# Sheet1.net
KiCad netlist of a schematic drawn in Altium Designer
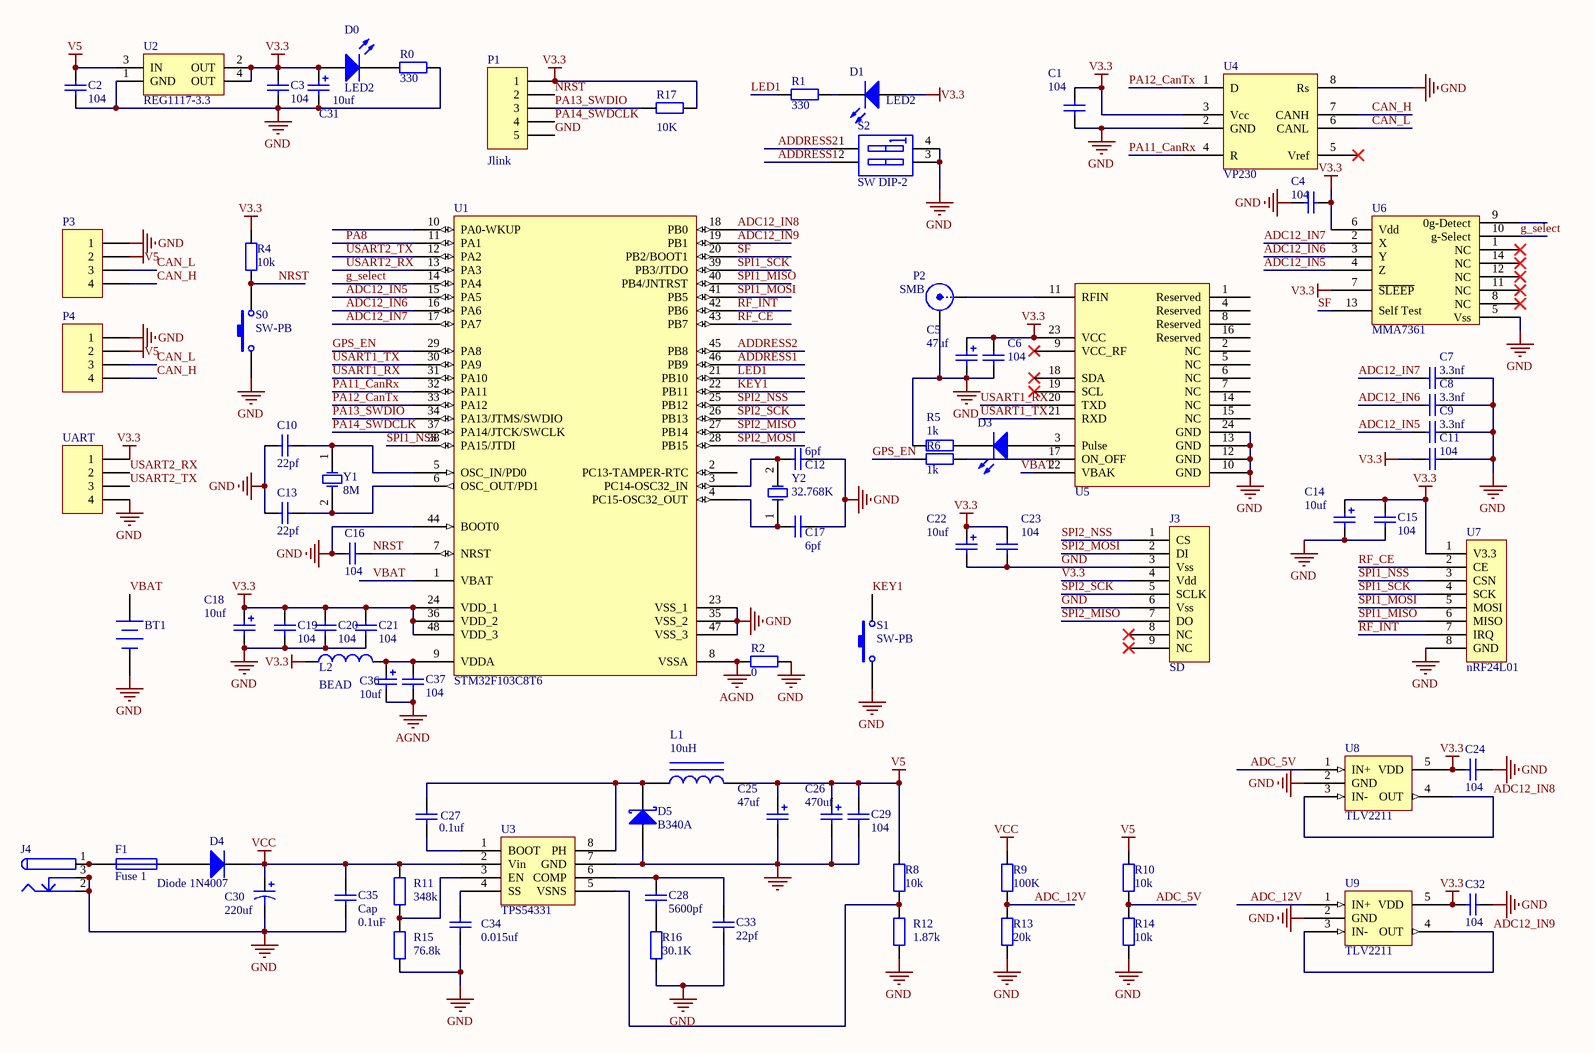
[diagram p0: Sheet1.SchDoc]

(export (version "E")
  (design (tool "Eeschema 10.0.6"))
  (components
    (comp (ref "BT1")
      (value "Battery")
      (footprint "LI1220_1")
      (description "Multicell Battery")
      (fields (field (name "PUBLISHER") "Altium Limited"))
      (libsource (lib "Miscellaneous Devices") (part "Battery"))
    )
    (comp (ref "C1")
      (value "104")
      (footprint "C0805")
      (description "Capacitor")
      (fields (field (name "Comment") "Cap") (field (name "PUBLISHER") "Altium Limited"))
      (libsource (lib "Miscellaneous Devices") (part "Cap"))
    )
    (comp (ref "C2")
      (value "104")
      (footprint "C0805")
      (description "Capacitor")
      (fields (field (name "Comment") "Cap") (field (name "PUBLISHER") "Altium Limited"))
      (libsource (lib "Miscellaneous Devices") (part "Cap"))
    )
    (comp (ref "C3")
      (value "104")
      (footprint "C0805")
      (description "Capacitor")
      (fields (field (name "Comment") "Cap") (field (name "PUBLISHER") "Altium Limited"))
      (libsource (lib "Miscellaneous Devices") (part "Cap"))
    )
    (comp (ref "C4")
      (value "104")
      (footprint "C0805")
      (description "Capacitor")
      (fields (field (name "Comment") "Cap") (field (name "PUBLISHER") "Altium Limited"))
      (libsource (lib "Miscellaneous Devices") (part "Cap"))
    )
    (comp (ref "C5")
      (value "47uf")
      (footprint "1812")
      (description "Polarized Capacitor (Axial)")
      (fields (field (name "Comment") "Cap Pol2") (field (name "PUBLISHER") "Altium Limited"))
      (libsource (lib "Miscellaneous Devices") (part "Cap Pol2"))
    )
    (comp (ref "C6")
      (value "104")
      (footprint "C0805")
      (description "Capacitor")
      (fields (field (name "Comment") "Cap") (field (name "PUBLISHER") "Altium Limited"))
      (libsource (lib "Miscellaneous Devices") (part "Cap"))
    )
    (comp (ref "C7")
      (value "3.3nf")
      (footprint "C0805")
      (description "Capacitor")
      (fields (field (name "Comment") "Cap") (field (name "PUBLISHER") "Altium Limited"))
      (libsource (lib "Miscellaneous Devices") (part "Cap"))
    )
    (comp (ref "C8")
      (value "3.3nf")
      (footprint "C0805")
      (description "Capacitor")
      (fields (field (name "Comment") "Cap") (field (name "PUBLISHER") "Altium Limited"))
      (libsource (lib "Miscellaneous Devices") (part "Cap"))
    )
    (comp (ref "C9")
      (value "3.3nf")
      (footprint "C0805")
      (description "Capacitor")
      (fields (field (name "Comment") "Cap") (field (name "PUBLISHER") "Altium Limited"))
      (libsource (lib "Miscellaneous Devices") (part "Cap"))
    )
    (comp (ref "C10")
      (value "22pf")
      (footprint "C0805")
      (description "Capacitor")
      (fields (field (name "Comment") "Cap") (field (name "PUBLISHER") "Altium Limited"))
      (libsource (lib "Miscellaneous Devices") (part "Cap"))
    )
    (comp (ref "C11")
      (value "104")
      (footprint "C0805")
      (description "Capacitor")
      (fields (field (name "Comment") "Cap") (field (name "PUBLISHER") "Altium Limited"))
      (libsource (lib "Miscellaneous Devices") (part "Cap"))
    )
    (comp (ref "C12")
      (value "6pf")
      (footprint "C0805")
      (description "Capacitor")
      (fields (field (name "Comment") "Cap") (field (name "PUBLISHER") "Altium Limited"))
      (libsource (lib "Miscellaneous Devices") (part "Cap"))
    )
    (comp (ref "C13")
      (value "22pf")
      (footprint "C0805")
      (description "Capacitor")
      (fields (field (name "Comment") "Cap") (field (name "PUBLISHER") "Altium Limited"))
      (libsource (lib "Miscellaneous Devices") (part "Cap"))
    )
    (comp (ref "C14")
      (value "10uf")
      (footprint "1206")
      (description "Polarized Capacitor (Axial)")
      (fields (field (name "Comment") "Cap Pol2") (field (name "PUBLISHER") "Altium Limited"))
      (libsource (lib "Miscellaneous Devices") (part "Cap Pol2"))
    )
    (comp (ref "C15")
      (value "104")
      (footprint "C0805")
      (description "Capacitor")
      (fields (field (name "Comment") "Cap") (field (name "PUBLISHER") "Altium Limited"))
      (libsource (lib "Miscellaneous Devices") (part "Cap"))
    )
    (comp (ref "C16")
      (value "104")
      (footprint "C0805")
      (description "Capacitor")
      (fields (field (name "Comment") "Cap") (field (name "PUBLISHER") "Altium Limited"))
      (libsource (lib "Miscellaneous Devices") (part "Cap"))
    )
    (comp (ref "C17")
      (value "6pf")
      (footprint "C0805")
      (description "Capacitor")
      (fields (field (name "Comment") "Cap") (field (name "PUBLISHER") "Altium Limited"))
      (libsource (lib "Miscellaneous Devices") (part "Cap"))
    )
    (comp (ref "C18")
      (value "10uf")
      (footprint "1206")
      (description "Polarized Capacitor (Axial)")
      (fields (field (name "Comment") "Cap Pol2") (field (name "PUBLISHER") "Altium Limited"))
      (libsource (lib "Miscellaneous Devices") (part "Cap Pol2"))
    )
    (comp (ref "C19")
      (value "104")
      (footprint "C0805")
      (description "Capacitor")
      (fields (field (name "Comment") "Cap") (field (name "PUBLISHER") "Altium Limited"))
      (libsource (lib "Miscellaneous Devices") (part "Cap"))
    )
    (comp (ref "C20")
      (value "104")
      (footprint "C0805")
      (description "Capacitor")
      (fields (field (name "Comment") "Cap") (field (name "PUBLISHER") "Altium Limited"))
      (libsource (lib "Miscellaneous Devices") (part "Cap"))
    )
    (comp (ref "C21")
      (value "104")
      (footprint "C0805")
      (description "Capacitor")
      (fields (field (name "Comment") "Cap") (field (name "PUBLISHER") "Altium Limited"))
      (libsource (lib "Miscellaneous Devices") (part "Cap"))
    )
    (comp (ref "C22")
      (value "10uf")
      (footprint "1206")
      (description "Polarized Capacitor (Axial)")
      (fields (field (name "Comment") "Cap Pol2") (field (name "PUBLISHER") "Altium Limited"))
      (libsource (lib "Miscellaneous Devices") (part "Cap Pol2"))
    )
    (comp (ref "C23")
      (value "104")
      (footprint "C0805")
      (description "Capacitor")
      (fields (field (name "Comment") "Cap") (field (name "PUBLISHER") "Altium Limited"))
      (libsource (lib "Miscellaneous Devices") (part "Cap"))
    )
    (comp (ref "C24")
      (value "104")
      (footprint "C0805")
      (description "Capacitor")
      (fields (field (name "Comment") "Cap") (field (name "PUBLISHER") "Altium Limited"))
      (libsource (lib "Miscellaneous Devices") (part "Cap"))
    )
    (comp (ref "C25")
      (value "47uf")
      (footprint "1812")
      (description "Polarized Capacitor (Axial)")
      (fields (field (name "Comment") "Cap Pol2") (field (name "PUBLISHER") "Altium Limited"))
      (libsource (lib "Miscellaneous Devices") (part "Cap Pol2"))
    )
    (comp (ref "C26")
      (value "470uf")
      (footprint "Cap8*8")
      (description "Polarized Capacitor (Axial)")
      (fields (field (name "Comment") "Cap Pol2") (field (name "PUBLISHER") "Altium Limited"))
      (libsource (lib "Miscellaneous Devices") (part "Cap Pol2"))
    )
    (comp (ref "C27")
      (value "0.1uf")
      (footprint "C0805")
      (description "Capacitor")
      (fields (field (name "Comment") "Cap") (field (name "PUBLISHER") "Altium Limited"))
      (libsource (lib "Miscellaneous Devices") (part "Cap"))
    )
    (comp (ref "C28")
      (value "5600pf")
      (footprint "C0805")
      (description "Capacitor")
      (fields (field (name "Comment") "Cap") (field (name "PUBLISHER") "Altium Limited"))
      (libsource (lib "Miscellaneous Devices") (part "Cap"))
    )
    (comp (ref "C29")
      (value "104")
      (footprint "C0805")
      (description "Capacitor")
      (fields (field (name "Comment") "Cap") (field (name "PUBLISHER") "Altium Limited"))
      (libsource (lib "Miscellaneous Devices") (part "Cap"))
    )
    (comp (ref "C30")
      (value "220uf")
      (footprint "Cap8*8")
      (description "Polarized Capacitor (Radial)")
      (fields (field (name "Comment") "Cap Pol1") (field (name "PUBLISHER") "Altium Limited"))
      (libsource (lib "Miscellaneous Devices") (part "Cap Pol1"))
    )
    (comp (ref "C31")
      (value "10uf")
      (footprint "1206")
      (description "Polarized Capacitor (Axial)")
      (fields (field (name "Comment") "Cap Pol2") (field (name "PUBLISHER") "Altium Limited"))
      (libsource (lib "Miscellaneous Devices") (part "Cap Pol2"))
    )
    (comp (ref "C32")
      (value "104")
      (footprint "C0805")
      (description "Capacitor")
      (fields (field (name "Comment") "Cap") (field (name "PUBLISHER") "Altium Limited"))
      (libsource (lib "Miscellaneous Devices") (part "Cap"))
    )
    (comp (ref "C33")
      (value "22pf")
      (footprint "C0805")
      (description "Capacitor")
      (fields (field (name "Comment") "Cap") (field (name "PUBLISHER") "Altium Limited"))
      (libsource (lib "Miscellaneous Devices") (part "Cap"))
    )
    (comp (ref "C34")
      (value "0.015uf")
      (footprint "C0805")
      (description "Capacitor")
      (fields (field (name "Comment") "Cap") (field (name "PUBLISHER") "Altium Limited"))
      (libsource (lib "Miscellaneous Devices") (part "Cap"))
    )
    (comp (ref "C35")
      (value "Cap")
      (footprint "C0805")
      (description "Capacitor")
      (fields (field (name "ALTIUM_VALUE") "0.1uF") (field (name "PUBLISHER") "Altium Limited"))
      (libsource (lib "Miscellaneous Devices") (part "Cap"))
    )
    (comp (ref "C36")
      (value "10uf")
      (footprint "1206")
      (description "Polarized Capacitor (Axial)")
      (fields (field (name "Comment") "Cap Pol2") (field (name "PUBLISHER") "Altium Limited"))
      (libsource (lib "Miscellaneous Devices") (part "Cap Pol2"))
    )
    (comp (ref "C37")
      (value "104")
      (footprint "C0805")
      (description "Capacitor")
      (fields (field (name "Comment") "Cap") (field (name "PUBLISHER") "Altium Limited"))
      (libsource (lib "Miscellaneous Devices") (part "Cap"))
    )
    (comp (ref "D0")
      (value "LED2")
      (footprint "C0805")
      (description "Typical RED, GREEN, YELLOW, AMBER GaAs LED")
      (fields (field (name "PUBLISHER") "Altium Limited"))
      (libsource (lib "Miscellaneous Devices") (part "LED2"))
    )
    (comp (ref "D1")
      (value "LED2")
      (footprint "C0805")
      (description "Typical RED, GREEN, YELLOW, AMBER GaAs LED")
      (fields (field (name "PUBLISHER") "Altium Limited"))
      (libsource (lib "Miscellaneous Devices") (part "LED2"))
    )
    (comp (ref "D3")
      (value "LED2")
      (footprint "C0805")
      (description "Typical RED, GREEN, YELLOW, AMBER GaAs LED")
      (fields (field (name "PUBLISHER") "Altium Limited"))
      (libsource (lib "Miscellaneous Devices") (part "LED2"))
    )
    (comp (ref "D4")
      (value "Diode 1N4007")
      (footprint "SMB")
      (description "1 Amp General Purpose Rectifier")
      (fields (field (name "PUBLISHER") "Altium Limited"))
      (libsource (lib "Miscellaneous Devices") (part "Diode 1N4007"))
    )
    (comp (ref "D5")
      (value "B340A")
      (footprint "SMB")
      (description "Schottky Rectifier")
      (fields (field (name "PUBLISHER") "Altium Limited"))
      (libsource (lib "Miscellaneous Devices") (part "Diode 11DQ03"))
    )
    (comp (ref "F1")
      (value "Fuse 1")
      (footprint "1812")
      (description "Fuse")
      (fields (field (name "PUBLISHER") "Altium Limited"))
      (libsource (lib "Miscellaneous Devices") (part "Fuse 1"))
    )
    (comp (ref "J3")
      (value "SD")
      (footprint "SD_LOCK")
      (description "Full-size SD Memory Card")
      (libsource (lib "HRT") (part "SD"))
    )
    (comp (ref "J4")
      (value "PWR2.5")
      (footprint "KLD-0202")
      (description "Low Voltage Power Supply Connector")
      (fields (field (name "PUBLISHER") "Altium Limited"))
      (libsource (lib "Miscellaneous Connectors") (part "PWR2.5"))
    )
    (comp (ref "L1")
      (value "10uH")
      (footprint "l")
      (description "Magnetic-Core Inductor")
      (fields (field (name "Comment") "Inductor Iron") (field (name "PUBLISHER") "Altium Limited"))
      (libsource (lib "Miscellaneous Devices") (part "Inductor Iron"))
    )
    (comp (ref "L2")
      (value "BEAD")
      (footprint "C0805")
      (description "Inductor")
      (fields (field (name "PUBLISHER") "Altium Limited"))
      (libsource (lib "Miscellaneous Devices") (part "Inductor"))
    )
    (comp (ref "P1")
      (value "Jlink")
      (footprint "HDR1X5")
      (description "Header, 5-Pin")
      (fields (field (name "PUBLISHER") "Altium Limited"))
      (libsource (lib "Miscellaneous Connectors") (part "Header 5"))
    )
    (comp (ref "P2")
      (value "SMB")
      (footprint "SMB_V-RJ45")
      (description "SMB Straight Connector")
      (fields (field (name "PUBLISHER") "Altium Limited"))
      (libsource (lib "Miscellaneous Connectors") (part "SMB"))
    )
    (comp (ref "P3")
      (value "Header 4")
      (footprint "DuraClik*4")
      (description "Header, 4-Pin")
      (fields (field (name "PUBLISHER") "Altium Limited"))
      (libsource (lib "Miscellaneous Connectors") (part "Header 4"))
    )
    (comp (ref "P4")
      (value "Header 4")
      (footprint "DuraClik*4")
      (description "Header, 4-Pin")
      (fields (field (name "PUBLISHER") "Altium Limited"))
      (libsource (lib "Miscellaneous Connectors") (part "Header 4"))
    )
    (comp (ref "R0")
      (value "330")
      (footprint "C0805")
      (description "Resistor")
      (fields (field (name "Comment") "Res2") (field (name "PUBLISHER") "Altium Limited"))
      (libsource (lib "") (part "Res2_1"))
    )
    (comp (ref "R1")
      (value "330")
      (footprint "C0805")
      (description "Resistor")
      (fields (field (name "Comment") "Res2") (field (name "PUBLISHER") "Altium Limited"))
      (libsource (lib "") (part "Res2_1"))
    )
    (comp (ref "R2")
      (value "0")
      (footprint "C0805")
      (description "Resistor")
      (fields (field (name "Comment") "Res2") (field (name "PUBLISHER") "Altium Limited"))
      (libsource (lib "") (part "Res2_2"))
    )
    (comp (ref "R4")
      (value "10k")
      (footprint "C0805")
      (description "Resistor")
      (fields (field (name "Comment") "Res2") (field (name "PUBLISHER") "Altium Limited"))
      (libsource (lib "Miscellaneous Devices") (part "Res2"))
    )
    (comp (ref "R5")
      (value "1k")
      (footprint "C0805")
      (description "Resistor")
      (fields (field (name "Comment") "Res2") (field (name "PUBLISHER") "Altium Limited"))
      (libsource (lib "") (part "Res2_1"))
    )
    (comp (ref "R6")
      (value "1k")
      (footprint "C0805")
      (description "Resistor")
      (fields (field (name "Comment") "Res2") (field (name "PUBLISHER") "Altium Limited"))
      (libsource (lib "") (part "Res2_2"))
    )
    (comp (ref "R8")
      (value "10k")
      (footprint "C0805")
      (description "Resistor")
      (fields (field (name "Comment") "Res2") (field (name "PUBLISHER") "Altium Limited"))
      (libsource (lib "Miscellaneous Devices") (part "Res2"))
    )
    (comp (ref "R9")
      (value "100K")
      (footprint "C0805")
      (description "Resistor")
      (fields (field (name "Comment") "Res2") (field (name "PUBLISHER") "Altium Limited"))
      (libsource (lib "Miscellaneous Devices") (part "Res2"))
    )
    (comp (ref "R10")
      (value "10k")
      (footprint "C0805")
      (description "Resistor")
      (fields (field (name "Comment") "Res2") (field (name "PUBLISHER") "Altium Limited"))
      (libsource (lib "Miscellaneous Devices") (part "Res2"))
    )
    (comp (ref "R11")
      (value "348k")
      (footprint "C0805")
      (description "Resistor")
      (fields (field (name "Comment") "Res2") (field (name "PUBLISHER") "Altium Limited"))
      (libsource (lib "Miscellaneous Devices") (part "Res2"))
    )
    (comp (ref "R12")
      (value "1.87k")
      (footprint "C0805")
      (description "Resistor")
      (fields (field (name "Comment") "Res2") (field (name "PUBLISHER") "Altium Limited"))
      (libsource (lib "Miscellaneous Devices") (part "Res2"))
    )
    (comp (ref "R13")
      (value "20k")
      (footprint "C0805")
      (description "Resistor")
      (fields (field (name "Comment") "Res2") (field (name "PUBLISHER") "Altium Limited"))
      (libsource (lib "Miscellaneous Devices") (part "Res2"))
    )
    (comp (ref "R14")
      (value "10k")
      (footprint "C0805")
      (description "Resistor")
      (fields (field (name "Comment") "Res2") (field (name "PUBLISHER") "Altium Limited"))
      (libsource (lib "Miscellaneous Devices") (part "Res2"))
    )
    (comp (ref "R15")
      (value "76.8k")
      (footprint "C0805")
      (description "Resistor")
      (fields (field (name "Comment") "Res2") (field (name "PUBLISHER") "Altium Limited"))
      (libsource (lib "Miscellaneous Devices") (part "Res2"))
    )
    (comp (ref "R16")
      (value "30.1K")
      (footprint "C0805")
      (description "Resistor")
      (fields (field (name "Comment") "Res2") (field (name "PUBLISHER") "Altium Limited"))
      (libsource (lib "Miscellaneous Devices") (part "Res2"))
    )
    (comp (ref "R17")
      (value "10K")
      (footprint "C0805")
      (description "Resistor")
      (fields (field (name "Comment") "Res2") (field (name "PUBLISHER") "Altium Limited"))
      (libsource (lib "") (part "Res2_1"))
    )
    (comp (ref "S0")
      (value "SW-PB")
      (footprint "button_SMD")
      (description "Switch")
      (fields (field (name "PUBLISHER") "Altium Limited"))
      (libsource (lib "Miscellaneous Devices") (part "SW-PB"))
    )
    (comp (ref "S1")
      (value "SW-PB")
      (footprint "button_SMD")
      (description "Switch")
      (fields (field (name "PUBLISHER") "Altium Limited"))
      (libsource (lib "Miscellaneous Devices") (part "SW-PB"))
    )
    (comp (ref "S2")
      (value "SW DIP-2")
      (footprint "DIP-4")
      (description "DIP Switch, 2 Position, SPST")
      (fields (field (name "PUBLISHER") "Altium Limited"))
      (libsource (lib "Miscellaneous Devices") (part "SW DIP-2"))
    )
    (comp (ref "U1")
      (value "STM32F103C8T6")
      (footprint "LQFP48_N")
      (description "STM32 ARM-based 32-bit MCU with 64 Kbytes Flash, 48-pin LQFP, Industrial Temperature")
      (fields (field (name "PUBLISHER") "Altium Limited"))
      (libsource (lib "ST Microcontroller 32-Bit STM32") (part "STM32F103C8T6"))
    )
    (comp (ref "U2")
      (value "REG1117-3.3")
      (footprint "ZZ311")
      (description "800mA and 1A Low Dropout Positive Regulator 2.85V, 3.3V, 5V, and Adjustable")
      (fields (field (name "PUBLISHER") "Altium Limited"))
      (libsource (lib "BB Power Mgt Voltage Regulator") (part "REG1117-3.3"))
    )
    (comp (ref "U3")
      (value "TPS54331")
      (footprint "SOIC8_M")
      (description "3A,28VINPUT, STEPDOWNSWIFT?DC/DCCONVERTERWITHECO-MODE?")
      (libsource (lib "HRT") (part "TPS54331"))
    )
    (comp (ref "U4")
      (value "VP230")
      (footprint "SOP8_N")
      (description "3.3-VCANTRANSCEIVERS")
      (libsource (lib "can") (part "VP230"))
    )
    (comp (ref "U5") (value "L20") (footprint "L20") (libsource (lib "Schlib1") (part "L20")))
    (comp (ref "U6")
      (value "MMA7361")
      (footprint "MMA7361 - duplicate")
      (libsource (lib "HRT") (part "MMA7361"))
    )
    (comp (ref "U7")
      (value "nRF24L01")
      (footprint "NRF24L01 PA")
      (description "nRF24L01+PA+LNA")
      (libsource (lib "HRT") (part "nRF24L01"))
    )
    (comp (ref "U8") (value "TLV2211") (footprint "SOT-23-5") (libsource (lib "Schlib1") (part "TLV2211")))
    (comp (ref "U9") (value "TLV2211") (footprint "SOT-23-5") (libsource (lib "Schlib1") (part "TLV2211")))
    (comp (ref "UART")
      (value "Header 4")
      (footprint "HDR1X4")
      (description "Header, 4-Pin")
      (fields (field (name "PUBLISHER") "Altium Limited"))
      (libsource (lib "Miscellaneous Connectors") (part "Header 4"))
    )
    (comp (ref "Y1")
      (value "8M")
      (footprint "XTAL")
      (description "Crystal Oscillator")
      (fields (field (name "PUBLISHER") "Altium Limited"))
      (libsource (lib "Miscellaneous Devices") (part "XTAL"))
    )
    (comp (ref "Y2")
      (value "32.768K")
      (footprint "XTAL32")
      (description "Crystal Oscillator")
      (fields (field (name "PUBLISHER") "Altium Limited"))
      (libsource (lib "Miscellaneous Devices") (part "XTAL"))
    )
  )
  (nets
    (net (code "1") (name "/ADC12_IN5") (class "Default")
      (node (ref "C9") (pin "1") (pinfunction "1_1") (pintype "passive"))
      (node (ref "U1") (pin "15") (pinfunction "PA5_15") (pintype "bidirectional"))
      (node (ref "U6") (pin "4") (pinfunction "Z_4") (pintype "passive"))
    )
    (net (code "2") (name "/ADC12_IN6") (class "Default")
      (node (ref "C8") (pin "1") (pinfunction "1_1") (pintype "passive"))
      (node (ref "U1") (pin "16") (pinfunction "PA6_16") (pintype "bidirectional"))
      (node (ref "U6") (pin "3") (pinfunction "Y_3") (pintype "passive"))
    )
    (net (code "3") (name "/ADC12_IN7") (class "Default")
      (node (ref "C7") (pin "1") (pinfunction "1_1") (pintype "passive"))
      (node (ref "U1") (pin "17") (pinfunction "PA7_17") (pintype "bidirectional"))
      (node (ref "U6") (pin "2") (pinfunction "X_2") (pintype "passive"))
    )
    (net (code "4") (name "/ADC12_IN8") (class "Default")
      (node (ref "U1") (pin "18") (pinfunction "PB0_18") (pintype "bidirectional"))
      (node (ref "U8") (pin "3") (pinfunction "IN-_3") (pintype "input"))
      (node (ref "U8") (pin "4") (pinfunction "OUT_4") (pintype "output"))
    )
    (net (code "5") (name "/ADC12_IN9") (class "Default")
      (node (ref "U1") (pin "19") (pinfunction "PB1_19") (pintype "bidirectional"))
      (node (ref "U9") (pin "3") (pinfunction "IN-_3") (pintype "input"))
      (node (ref "U9") (pin "4") (pinfunction "OUT_4") (pintype "output"))
    )
    (net (code "6") (name "/ADC_5V") (class "Default")
      (node (ref "R10") (pin "2") (pinfunction "2_2") (pintype "passive"))
      (node (ref "R14") (pin "1") (pinfunction "1_1") (pintype "passive"))
      (node (ref "U8") (pin "1") (pinfunction "IN+_1") (pintype "input"))
    )
    (net (code "7") (name "/ADC_12V") (class "Default")
      (node (ref "R13") (pin "1") (pinfunction "1_1") (pintype "passive"))
      (node (ref "R9") (pin "2") (pinfunction "2_2") (pintype "passive"))
      (node (ref "U9") (pin "1") (pinfunction "IN+_1") (pintype "input"))
    )
    (net (code "8") (name "/ADDRESS1") (class "Default")
      (node (ref "S2") (pin "2") (pinfunction "A2_2") (pintype "passive"))
      (node (ref "U1") (pin "46") (pinfunction "PB9_46") (pintype "bidirectional"))
    )
    (net (code "9") (name "/ADDRESS2") (class "Default")
      (node (ref "S2") (pin "1") (pinfunction "A1_1") (pintype "passive"))
      (node (ref "U1") (pin "45") (pinfunction "PB8_45") (pintype "bidirectional"))
    )
    (net (code "10") (name "/CAN_H") (class "Default")
      (node (ref "P3") (pin "4") (pinfunction "4_4") (pintype "passive"))
      (node (ref "P4") (pin "4") (pinfunction "4_4") (pintype "passive"))
      (node (ref "U4") (pin "7") (pinfunction "CANH_7") (pintype "passive"))
    )
    (net (code "11") (name "/CAN_L") (class "Default")
      (node (ref "P3") (pin "3") (pinfunction "3_3") (pintype "passive"))
      (node (ref "P4") (pin "3") (pinfunction "3_3") (pintype "passive"))
      (node (ref "U4") (pin "6") (pinfunction "CANL_6") (pintype "passive"))
    )
    (net (code "12") (name "/GPS_EN") (class "Default")
      (node (ref "R6") (pin "1") (pinfunction "1_1") (pintype "passive"))
      (node (ref "U1") (pin "29") (pinfunction "PA8_29") (pintype "bidirectional"))
    )
    (net (code "13") (name "/KEY1") (class "Default")
      (node (ref "S1") (pin "2") (pinfunction "2_2") (pintype "passive"))
      (node (ref "U1") (pin "22") (pinfunction "PB11_22") (pintype "bidirectional"))
    )
    (net (code "14") (name "/LED1") (class "Default")
      (node (ref "R1") (pin "2") (pinfunction "2_2") (pintype "passive"))
      (node (ref "U1") (pin "21") (pinfunction "PB10_21") (pintype "bidirectional"))
    )
    (net (code "15") (name "/NRST") (class "Default")
      (node (ref "C16") (pin "2") (pinfunction "2_2") (pintype "passive"))
      (node (ref "P1") (pin "2") (pinfunction "2_2") (pintype "passive"))
      (node (ref "R4") (pin "2") (pinfunction "2_2") (pintype "passive"))
      (node (ref "S0") (pin "2") (pinfunction "2_2") (pintype "passive"))
      (node (ref "U1") (pin "7") (pinfunction "NRST_7") (pintype "bidirectional"))
    )
    (net (code "16") (name "/PA8") (class "Default")
      (node (ref "U1") (pin "11") (pinfunction "PA1_11") (pintype "bidirectional"))
    )
    (net (code "17") (name "/PA11_CanRx") (class "Default")
      (node (ref "U1") (pin "32") (pinfunction "PA11_32") (pintype "bidirectional"))
      (node (ref "U4") (pin "4") (pinfunction "R_4") (pintype "passive"))
    )
    (net (code "18") (name "/PA12_CanTx") (class "Default")
      (node (ref "U1") (pin "33") (pinfunction "PA12_33") (pintype "bidirectional"))
      (node (ref "U4") (pin "1") (pinfunction "D_1") (pintype "passive"))
    )
    (net (code "19") (name "/PA13_SWDIO") (class "Default")
      (node (ref "P1") (pin "3") (pinfunction "3_3") (pintype "passive"))
      (node (ref "R17") (pin "2") (pinfunction "2_2") (pintype "passive"))
      (node (ref "U1") (pin "34") (pinfunction "PA13/JTMS/SWDIO_34") (pintype "bidirectional"))
    )
    (net (code "20") (name "/PA14_SWDCLK") (class "Default")
      (node (ref "P1") (pin "4") (pinfunction "4_4") (pintype "passive"))
      (node (ref "U1") (pin "37") (pinfunction "PA14/JTCK/SWCLK_37") (pintype "bidirectional"))
    )
    (net (code "21") (name "/RF_CE") (class "Default")
      (node (ref "U1") (pin "43") (pinfunction "PB7_43") (pintype "bidirectional"))
      (node (ref "U7") (pin "2") (pinfunction "CE_2") (pintype "passive"))
    )
    (net (code "22") (name "/RF_INT") (class "Default")
      (node (ref "U1") (pin "42") (pinfunction "PB6_42") (pintype "bidirectional"))
      (node (ref "U7") (pin "7") (pinfunction "IRQ_7") (pintype "passive"))
    )
    (net (code "23") (name "/SF") (class "Default")
      (node (ref "U1") (pin "20") (pinfunction "PB2/BOOT1_20") (pintype "bidirectional"))
      (node (ref "U6") (pin "13") (pinfunction "Self_Test_13") (pintype "passive"))
    )
    (net (code "24") (name "/SPI1_MISO") (class "Default")
      (node (ref "U1") (pin "40") (pinfunction "PB4/JNTRST_40") (pintype "bidirectional"))
      (node (ref "U7") (pin "6") (pinfunction "MISO_6") (pintype "passive"))
    )
    (net (code "25") (name "/SPI1_MOSI") (class "Default")
      (node (ref "U1") (pin "41") (pinfunction "PB5_41") (pintype "bidirectional"))
      (node (ref "U7") (pin "5") (pinfunction "MOSI_5") (pintype "passive"))
    )
    (net (code "26") (name "/SPI1_NSS") (class "Default")
      (node (ref "U1") (pin "38") (pinfunction "PA15/JTDI_38") (pintype "bidirectional"))
      (node (ref "U7") (pin "3") (pinfunction "CSN_3") (pintype "passive"))
    )
    (net (code "27") (name "/SPI1_SCK") (class "Default")
      (node (ref "U1") (pin "39") (pinfunction "PB3/JTDO_39") (pintype "bidirectional"))
      (node (ref "U7") (pin "4") (pinfunction "SCK_4") (pintype "passive"))
    )
    (net (code "28") (name "/SPI2_MISO") (class "Default")
      (node (ref "J3") (pin "7") (pinfunction "DO_7") (pintype "passive"))
      (node (ref "U1") (pin "27") (pinfunction "PB14_27") (pintype "bidirectional"))
    )
    (net (code "29") (name "/SPI2_MOSI") (class "Default")
      (node (ref "J3") (pin "2") (pinfunction "DI_2") (pintype "passive"))
      (node (ref "U1") (pin "28") (pinfunction "PB15_28") (pintype "bidirectional"))
    )
    (net (code "30") (name "/SPI2_NSS") (class "Default")
      (node (ref "J3") (pin "1") (pinfunction "CS_1") (pintype "passive"))
      (node (ref "U1") (pin "25") (pinfunction "PB12_25") (pintype "bidirectional"))
    )
    (net (code "31") (name "/SPI2_SCK") (class "Default")
      (node (ref "J3") (pin "5") (pinfunction "SCLK_5") (pintype "passive"))
      (node (ref "U1") (pin "26") (pinfunction "PB13_26") (pintype "bidirectional"))
    )
    (net (code "32") (name "/USART1_RX") (class "Default")
      (node (ref "U1") (pin "31") (pinfunction "PA10_31") (pintype "bidirectional"))
      (node (ref "U5") (pin "20") (pinfunction "TXD_20") (pintype "passive"))
    )
    (net (code "33") (name "/USART1_TX") (class "Default")
      (node (ref "U1") (pin "30") (pinfunction "PA9_30") (pintype "bidirectional"))
      (node (ref "U5") (pin "21") (pinfunction "RXD_21") (pintype "passive"))
    )
    (net (code "34") (name "/USART2_RX") (class "Default")
      (node (ref "U1") (pin "13") (pinfunction "PA3_13") (pintype "bidirectional"))
      (node (ref "UART") (pin "2") (pinfunction "2_2") (pintype "passive"))
    )
    (net (code "35") (name "/USART2_TX") (class "Default")
      (node (ref "U1") (pin "12") (pinfunction "PA2_12") (pintype "bidirectional"))
      (node (ref "UART") (pin "3") (pinfunction "3_3") (pintype "passive"))
    )
    (net (code "36") (name "/VBAT") (class "Default")
      (node (ref "BT1") (pin "1") (pinfunction "+_1") (pintype "passive"))
      (node (ref "U1") (pin "1") (pinfunction "VBAT_1") (pintype "power_in"))
      (node (ref "U5") (pin "22") (pinfunction "VBAK_22") (pintype "passive"))
    )
    (net (code "37") (name "/g_select") (class "Default")
      (node (ref "U1") (pin "14") (pinfunction "PA4_14") (pintype "bidirectional"))
      (node (ref "U6") (pin "10") (pinfunction "g-Select_10") (pintype "passive"))
    )
    (net (code "38") (name "AGND") (class "Default")
      (node (ref "C36") (pin "2") (pinfunction "2_2") (pintype "passive"))
      (node (ref "C37") (pin "2") (pinfunction "2_2") (pintype "passive"))
      (node (ref "R2") (pin "1") (pinfunction "1_1") (pintype "passive"))
      (node (ref "U1") (pin "8") (pinfunction "VSSA_8") (pintype "power_in"))
    )
    (net (code "39") (name "GND") (class "Default")
      (node (ref "BT1") (pin "2") (pinfunction "-_2") (pintype "passive"))
      (node (ref "C1") (pin "1") (pinfunction "1_1") (pintype "passive"))
      (node (ref "C10") (pin "1") (pinfunction "1_1") (pintype "passive"))
      (node (ref "C11") (pin "1") (pinfunction "1_1") (pintype "passive"))
      (node (ref "C12") (pin "1") (pinfunction "1_1") (pintype "passive"))
      (node (ref "C13") (pin "1") (pinfunction "1_1") (pintype "passive"))
      (node (ref "C14") (pin "2") (pinfunction "2_2") (pintype "passive"))
      (node (ref "C15") (pin "2") (pinfunction "2_2") (pintype "passive"))
      (node (ref "C16") (pin "1") (pinfunction "1_1") (pintype "passive"))
      (node (ref "C17") (pin "1") (pinfunction "1_1") (pintype "passive"))
      (node (ref "C18") (pin "2") (pinfunction "2_2") (pintype "passive"))
      (node (ref "C19") (pin "2") (pinfunction "2_2") (pintype "passive"))
      (node (ref "C2") (pin "2") (pinfunction "2_2") (pintype "passive"))
      (node (ref "C20") (pin "2") (pinfunction "2_2") (pintype "passive"))
      (node (ref "C21") (pin "2") (pinfunction "2_2") (pintype "passive"))
      (node (ref "C22") (pin "2") (pinfunction "2_2") (pintype "passive"))
      (node (ref "C23") (pin "2") (pinfunction "2_2") (pintype "passive"))
      (node (ref "C24") (pin "2") (pinfunction "2_2") (pintype "passive"))
      (node (ref "C25") (pin "2") (pinfunction "2_2") (pintype "passive"))
      (node (ref "C26") (pin "2") (pinfunction "2_2") (pintype "passive"))
      (node (ref "C29") (pin "1") (pinfunction "1_1") (pintype "passive"))
      (node (ref "C3") (pin "2") (pinfunction "2_2") (pintype "passive"))
      (node (ref "C30") (pin "2") (pinfunction "2_2") (pintype "passive"))
      (node (ref "C31") (pin "2") (pinfunction "2_2") (pintype "passive"))
      (node (ref "C32") (pin "2") (pinfunction "2_2") (pintype "passive"))
      (node (ref "C33") (pin "2") (pinfunction "2_2") (pintype "passive"))
      (node (ref "C34") (pin "2") (pinfunction "2_2") (pintype "passive"))
      (node (ref "C35") (pin "2") (pinfunction "2_2") (pintype "passive"))
      (node (ref "C4") (pin "1") (pinfunction "1_1") (pintype "passive"))
      (node (ref "C5") (pin "2") (pinfunction "2_2") (pintype "passive"))
      (node (ref "C6") (pin "1") (pinfunction "1_1") (pintype "passive"))
      (node (ref "C7") (pin "2") (pinfunction "2_2") (pintype "passive"))
      (node (ref "C8") (pin "2") (pinfunction "2_2") (pintype "passive"))
      (node (ref "C9") (pin "2") (pinfunction "2_2") (pintype "passive"))
      (node (ref "D5") (pin "1") (pinfunction "A_1") (pintype "passive"))
      (node (ref "J3") (pin "3") (pinfunction "Vss_3") (pintype "passive"))
      (node (ref "J3") (pin "6") (pinfunction "Vss_6") (pintype "passive"))
      (node (ref "J4") (pin "2") (pinfunction "2_2") (pintype "power_in"))
      (node (ref "J4") (pin "2A") (pinfunction "2A_2A") (pintype "power_in"))
      (node (ref "J4") (pin "2B") (pinfunction "2B_2B") (pintype "power_in"))
      (node (ref "J4") (pin "3") (pinfunction "3_3") (pintype "power_in"))
      (node (ref "J4") (pin "3A") (pinfunction "3A_3A") (pintype "power_in"))
      (node (ref "J4") (pin "3B") (pinfunction "3B_3B") (pintype "power_in"))
      (node (ref "P1") (pin "5") (pinfunction "5_5") (pintype "passive"))
      (node (ref "P2") (pin "2") (pinfunction "Y_2") (pintype "passive"))
      (node (ref "P3") (pin "1") (pinfunction "1_1") (pintype "passive"))
      (node (ref "P4") (pin "1") (pinfunction "1_1") (pintype "passive"))
      (node (ref "R0") (pin "1") (pinfunction "1_1") (pintype "passive"))
      (node (ref "R12") (pin "2") (pinfunction "2_2") (pintype "passive"))
      (node (ref "R13") (pin "2") (pinfunction "2_2") (pintype "passive"))
      (node (ref "R14") (pin "2") (pinfunction "2_2") (pintype "passive"))
      (node (ref "R15") (pin "2") (pinfunction "2_2") (pintype "passive"))
      (node (ref "R16") (pin "2") (pinfunction "2_2") (pintype "passive"))
      (node (ref "R2") (pin "2") (pinfunction "2_2") (pintype "passive"))
      (node (ref "R5") (pin "2") (pinfunction "2_2") (pintype "passive"))
      (node (ref "S0") (pin "1") (pinfunction "1_1") (pintype "passive"))
      (node (ref "S1") (pin "1") (pinfunction "1_1") (pintype "passive"))
      (node (ref "S2") (pin "3") (pinfunction "B2_3") (pintype "passive"))
      (node (ref "S2") (pin "4") (pinfunction "B1_4") (pintype "passive"))
      (node (ref "U1") (pin "23") (pinfunction "VSS_1_23") (pintype "power_in"))
      (node (ref "U1") (pin "35") (pinfunction "VSS_2_35") (pintype "power_in"))
      (node (ref "U1") (pin "44") (pinfunction "BOOT0_44") (pintype "input"))
      (node (ref "U1") (pin "47") (pinfunction "VSS_3_47") (pintype "power_in"))
      (node (ref "U2") (pin "1") (pinfunction "GND_1") (pintype "power_in"))
      (node (ref "U3") (pin "7") (pinfunction "GND_7") (pintype "passive"))
      (node (ref "U4") (pin "2") (pinfunction "GND_2") (pintype "passive"))
      (node (ref "U4") (pin "8") (pinfunction "Rs_8") (pintype "passive"))
      (node (ref "U5") (pin "10") (pinfunction "GND_10") (pintype "passive"))
      (node (ref "U5") (pin "12") (pinfunction "GND_12") (pintype "passive"))
      (node (ref "U5") (pin "13") (pinfunction "GND_13") (pintype "passive"))
      (node (ref "U5") (pin "24") (pinfunction "GND_24") (pintype "passive"))
      (node (ref "U6") (pin "5") (pinfunction "Vss_5") (pintype "passive"))
      (node (ref "U7") (pin "8") (pinfunction "GND_8") (pintype "passive"))
      (node (ref "U8") (pin "2") (pinfunction "GND_2") (pintype "power_in"))
      (node (ref "U9") (pin "2") (pinfunction "GND_2") (pintype "power_in"))
      (node (ref "UART") (pin "4") (pinfunction "4_4") (pintype "passive"))
    )
    (net (code "40") (name "Net-(C28-Pad2)") (class "Default")
      (node (ref "C28") (pin "2") (pinfunction "2_2") (pintype "passive"))
      (node (ref "R16") (pin "1") (pinfunction "1_1") (pintype "passive"))
    )
    (net (code "41") (name "Net-(D0-K)") (class "Default")
      (node (ref "D0") (pin "2") (pinfunction "K_2") (pintype "passive"))
      (node (ref "R0") (pin "2") (pinfunction "2_2") (pintype "passive"))
    )
    (net (code "42") (name "Net-(D1-K)") (class "Default")
      (node (ref "D1") (pin "2") (pinfunction "K_2") (pintype "passive"))
      (node (ref "R1") (pin "1") (pinfunction "1_1") (pintype "passive"))
    )
    (net (code "43") (name "Net-(D3-A)") (class "Default")
      (node (ref "D3") (pin "1") (pinfunction "A_1") (pintype "passive"))
      (node (ref "U5") (pin "3") (pinfunction "Pulse_3") (pintype "passive"))
    )
    (net (code "44") (name "Net-(D3-K)") (class "Default")
      (node (ref "D3") (pin "2") (pinfunction "K_2") (pintype "passive"))
      (node (ref "R5") (pin "1") (pinfunction "1_1") (pintype "passive"))
    )
    (net (code "45") (name "Net-(D4-Pad1)") (class "Default")
      (node (ref "D4") (pin "1") (pinfunction "1_1") (pintype "passive"))
      (node (ref "F1") (pin "2") (pinfunction "2_2") (pintype "passive"))
    )
    (net (code "46") (name "Net-(D5-K)") (class "Default")
      (node (ref "C27") (pin "1") (pinfunction "1_1") (pintype "passive"))
      (node (ref "D5") (pin "2") (pinfunction "K_2") (pintype "passive"))
      (node (ref "L1") (pin "1") (pinfunction "1_1") (pintype "passive"))
      (node (ref "U3") (pin "8") (pinfunction "PH_8") (pintype "passive"))
    )
    (net (code "47") (name "Net-(F1-Pad1)") (class "Default")
      (node (ref "F1") (pin "1") (pinfunction "1_1") (pintype "passive"))
      (node (ref "J4") (pin "1") (pinfunction "1_1") (pintype "power_in"))
      (node (ref "J4") (pin "1A") (pinfunction "1A_1A") (pintype "power_in"))
      (node (ref "J4") (pin "1B") (pinfunction "1B_1B") (pintype "power_in"))
    )
    (net (code "48") (name "Net-(P2-X)") (class "Default")
      (node (ref "P2") (pin "1") (pinfunction "X_1") (pintype "passive"))
      (node (ref "U5") (pin "11") (pinfunction "RFIN_11") (pintype "passive"))
    )
    (net (code "49") (name "Net-(U1-OSC_IN{slash}PD0)") (class "Default")
      (node (ref "C10") (pin "2") (pinfunction "2_2") (pintype "passive"))
      (node (ref "U1") (pin "5") (pinfunction "OSC_IN/PD0_5") (pintype "input"))
      (node (ref "Y1") (pin "1") (pinfunction "OSC1_1") (pintype "passive"))
    )
    (net (code "50") (name "Net-(U1-OSC_OUT{slash}PD1)") (class "Default")
      (node (ref "C13") (pin "2") (pinfunction "2_2") (pintype "passive"))
      (node (ref "U1") (pin "6") (pinfunction "OSC_OUT/PD1_6") (pintype "output"))
      (node (ref "Y1") (pin "2") (pinfunction "OSC2_2") (pintype "passive"))
    )
    (net (code "51") (name "Net-(U1-PC14-OSC32_IN)") (class "Default")
      (node (ref "C12") (pin "2") (pinfunction "2_2") (pintype "passive"))
      (node (ref "U1") (pin "3") (pinfunction "PC14-OSC32_IN_3") (pintype "bidirectional"))
      (node (ref "Y2") (pin "2") (pinfunction "OSC2_2") (pintype "passive"))
    )
    (net (code "52") (name "Net-(U1-PC15-OSC32_OUT)") (class "Default")
      (node (ref "C17") (pin "2") (pinfunction "2_2") (pintype "passive"))
      (node (ref "U1") (pin "4") (pinfunction "PC15-OSC32_OUT_4") (pintype "bidirectional"))
      (node (ref "Y2") (pin "1") (pinfunction "OSC1_1") (pintype "passive"))
    )
    (net (code "53") (name "Net-(U1-VDDA)") (class "Default")
      (node (ref "C36") (pin "1") (pinfunction "1_1") (pintype "passive"))
      (node (ref "C37") (pin "1") (pinfunction "1_1") (pintype "passive"))
      (node (ref "L2") (pin "2") (pinfunction "2_2") (pintype "passive"))
      (node (ref "U1") (pin "9") (pinfunction "VDDA_9") (pintype "power_in"))
    )
    (net (code "54") (name "Net-(U3-BOOT)") (class "Default")
      (node (ref "C27") (pin "2") (pinfunction "2_2") (pintype "passive"))
      (node (ref "U3") (pin "1") (pinfunction "BOOT_1") (pintype "passive"))
    )
    (net (code "55") (name "Net-(U3-COMP)") (class "Default")
      (node (ref "C28") (pin "1") (pinfunction "1_1") (pintype "passive"))
      (node (ref "C33") (pin "1") (pinfunction "1_1") (pintype "passive"))
      (node (ref "U3") (pin "6") (pinfunction "COMP_6") (pintype "passive"))
    )
    (net (code "56") (name "Net-(U3-EN)") (class "Default")
      (node (ref "R11") (pin "2") (pinfunction "2_2") (pintype "passive"))
      (node (ref "R15") (pin "1") (pinfunction "1_1") (pintype "passive"))
      (node (ref "U3") (pin "3") (pinfunction "EN_3") (pintype "passive"))
    )
    (net (code "57") (name "Net-(U3-SS)") (class "Default")
      (node (ref "C34") (pin "1") (pinfunction "1_1") (pintype "passive"))
      (node (ref "U3") (pin "4") (pinfunction "SS_4") (pintype "passive"))
    )
    (net (code "58") (name "Net-(U3-VSNS)") (class "Default")
      (node (ref "R12") (pin "1") (pinfunction "1_1") (pintype "passive"))
      (node (ref "R8") (pin "2") (pinfunction "2_2") (pintype "passive"))
      (node (ref "U3") (pin "5") (pinfunction "VSNS_5") (pintype "passive"))
    )
    (net (code "59") (name "Net-(U5-ON_OFF)") (class "Default")
      (node (ref "R6") (pin "2") (pinfunction "2_2") (pintype "passive"))
      (node (ref "U5") (pin "17") (pinfunction "ON_OFF_17") (pintype "passive"))
    )
    (net (code "60") (name "V3.3") (class "Default")
      (node (ref "C1") (pin "2") (pinfunction "2_2") (pintype "passive"))
      (node (ref "C11") (pin "2") (pinfunction "2_2") (pintype "passive"))
      (node (ref "C14") (pin "1") (pinfunction "1_1") (pintype "passive"))
      (node (ref "C15") (pin "1") (pinfunction "1_1") (pintype "passive"))
      (node (ref "C18") (pin "1") (pinfunction "1_1") (pintype "passive"))
      (node (ref "C19") (pin "1") (pinfunction "1_1") (pintype "passive"))
      (node (ref "C20") (pin "1") (pinfunction "1_1") (pintype "passive"))
      (node (ref "C21") (pin "1") (pinfunction "1_1") (pintype "passive"))
      (node (ref "C22") (pin "1") (pinfunction "1_1") (pintype "passive"))
      (node (ref "C23") (pin "1") (pinfunction "1_1") (pintype "passive"))
      (node (ref "C24") (pin "1") (pinfunction "1_1") (pintype "passive"))
      (node (ref "C3") (pin "1") (pinfunction "1_1") (pintype "passive"))
      (node (ref "C31") (pin "1") (pinfunction "1_1") (pintype "passive"))
      (node (ref "C32") (pin "1") (pinfunction "1_1") (pintype "passive"))
      (node (ref "C4") (pin "2") (pinfunction "2_2") (pintype "passive"))
      (node (ref "C5") (pin "1") (pinfunction "1_1") (pintype "passive"))
      (node (ref "C6") (pin "2") (pinfunction "2_2") (pintype "passive"))
      (node (ref "D0") (pin "1") (pinfunction "A_1") (pintype "passive"))
      (node (ref "D1") (pin "1") (pinfunction "A_1") (pintype "passive"))
      (node (ref "J3") (pin "4") (pinfunction "Vdd_4") (pintype "passive"))
      (node (ref "L2") (pin "1") (pinfunction "1_1") (pintype "passive"))
      (node (ref "P1") (pin "1") (pinfunction "1_1") (pintype "passive"))
      (node (ref "R17") (pin "1") (pinfunction "1_1") (pintype "passive"))
      (node (ref "R4") (pin "1") (pinfunction "1_1") (pintype "passive"))
      (node (ref "U1") (pin "24") (pinfunction "VDD_1_24") (pintype "power_in"))
      (node (ref "U1") (pin "36") (pinfunction "VDD_2_36") (pintype "power_in"))
      (node (ref "U1") (pin "48") (pinfunction "VDD_3_48") (pintype "power_in"))
      (node (ref "U2") (pin "2") (pinfunction "OUT_2") (pintype "power_in"))
      (node (ref "U2") (pin "4") (pinfunction "OUT_4") (pintype "power_in"))
      (node (ref "U4") (pin "3") (pinfunction "Vcc_3") (pintype "passive"))
      (node (ref "U5") (pin "23") (pinfunction "VCC_23") (pintype "passive"))
      (node (ref "U6") (pin "6") (pinfunction "Vdd_6") (pintype "passive"))
      (node (ref "U6") (pin "7") (pinfunction "~{SLEEP}_7") (pintype "passive"))
      (node (ref "U7") (pin "1") (pinfunction "V3.3_1") (pintype "passive"))
      (node (ref "U8") (pin "5") (pinfunction "VDD_5") (pintype "power_in"))
      (node (ref "U9") (pin "5") (pinfunction "VDD_5") (pintype "power_in"))
      (node (ref "UART") (pin "1") (pinfunction "1_1") (pintype "passive"))
    )
    (net (code "61") (name "V5") (class "Default")
      (node (ref "C2") (pin "1") (pinfunction "1_1") (pintype "passive"))
      (node (ref "C25") (pin "1") (pinfunction "1_1") (pintype "passive"))
      (node (ref "C26") (pin "1") (pinfunction "1_1") (pintype "passive"))
      (node (ref "C29") (pin "2") (pinfunction "2_2") (pintype "passive"))
      (node (ref "L1") (pin "2") (pinfunction "2_2") (pintype "passive"))
      (node (ref "P3") (pin "2") (pinfunction "2_2") (pintype "passive"))
      (node (ref "P4") (pin "2") (pinfunction "2_2") (pintype "passive"))
      (node (ref "R10") (pin "1") (pinfunction "1_1") (pintype "passive"))
      (node (ref "R8") (pin "1") (pinfunction "1_1") (pintype "passive"))
      (node (ref "U2") (pin "3") (pinfunction "IN_3") (pintype "power_in"))
    )
    (net (code "62") (name "VCC") (class "Default")
      (node (ref "C30") (pin "1") (pinfunction "1_1") (pintype "passive"))
      (node (ref "C35") (pin "1") (pinfunction "1_1") (pintype "passive"))
      (node (ref "D4") (pin "2") (pinfunction "2_2") (pintype "passive"))
      (node (ref "R11") (pin "1") (pinfunction "1_1") (pintype "passive"))
      (node (ref "R9") (pin "1") (pinfunction "1_1") (pintype "passive"))
      (node (ref "U3") (pin "2") (pinfunction "Vin_2") (pintype "passive"))
    )
    (net (code "63") (name "unconnected-(J3-NC-Pad8)") (class "Default")
      (node (ref "J3") (pin "8") (pinfunction "NC_8") (pintype "passive+no_connect"))
    )
    (net (code "64") (name "unconnected-(J3-NC-Pad9)") (class "Default")
      (node (ref "J3") (pin "9") (pinfunction "NC_9") (pintype "passive+no_connect"))
    )
    (net (code "65") (name "unconnected-(U1-PA0-WKUP-Pad10)") (class "Default")
      (node (ref "U1") (pin "10") (pinfunction "PA0-WKUP_10") (pintype "bidirectional"))
    )
    (net (code "66") (name "unconnected-(U1-PC13-TAMPER-RTC-Pad2)") (class "Default")
      (node (ref "U1") (pin "2") (pinfunction "PC13-TAMPER-RTC_2") (pintype "bidirectional"))
    )
    (net (code "67") (name "unconnected-(U4-Vref-Pad5)") (class "Default")
      (node (ref "U4") (pin "5") (pinfunction "Vref_5") (pintype "passive+no_connect"))
    )
    (net (code "68") (name "unconnected-(U5-NC-Pad2)") (class "Default")
      (node (ref "U5") (pin "2") (pinfunction "NC_2") (pintype "passive"))
    )
    (net (code "69") (name "unconnected-(U5-NC-Pad5)") (class "Default")
      (node (ref "U5") (pin "5") (pinfunction "NC_5") (pintype "passive"))
    )
    (net (code "70") (name "unconnected-(U5-NC-Pad6)") (class "Default")
      (node (ref "U5") (pin "6") (pinfunction "NC_6") (pintype "passive"))
    )
    (net (code "71") (name "unconnected-(U5-NC-Pad7)") (class "Default")
      (node (ref "U5") (pin "7") (pinfunction "NC_7") (pintype "passive"))
    )
    (net (code "72") (name "unconnected-(U5-NC-Pad14)") (class "Default")
      (node (ref "U5") (pin "14") (pinfunction "NC_14") (pintype "passive"))
    )
    (net (code "73") (name "unconnected-(U5-NC-Pad15)") (class "Default")
      (node (ref "U5") (pin "15") (pinfunction "NC_15") (pintype "passive"))
    )
    (net (code "74") (name "unconnected-(U5-Reserved-Pad1)") (class "Default")
      (node (ref "U5") (pin "1") (pinfunction "Reserved_1") (pintype "passive"))
    )
    (net (code "75") (name "unconnected-(U5-Reserved-Pad4)") (class "Default")
      (node (ref "U5") (pin "4") (pinfunction "Reserved_4") (pintype "passive"))
    )
    (net (code "76") (name "unconnected-(U5-Reserved-Pad8)") (class "Default")
      (node (ref "U5") (pin "8") (pinfunction "Reserved_8") (pintype "passive"))
    )
    (net (code "77") (name "unconnected-(U5-Reserved-Pad16)") (class "Default")
      (node (ref "U5") (pin "16") (pinfunction "Reserved_16") (pintype "passive"))
    )
    (net (code "78") (name "unconnected-(U5-SCL-Pad19)") (class "Default")
      (node (ref "U5") (pin "19") (pinfunction "SCL_19") (pintype "passive+no_connect"))
    )
    (net (code "79") (name "unconnected-(U5-SDA-Pad18)") (class "Default")
      (node (ref "U5") (pin "18") (pinfunction "SDA_18") (pintype "passive+no_connect"))
    )
    (net (code "80") (name "unconnected-(U5-VCC_RF-Pad9)") (class "Default")
      (node (ref "U5") (pin "9") (pinfunction "VCC_RF_9") (pintype "passive+no_connect"))
    )
    (net (code "81") (name "unconnected-(U6-0g-Detect-Pad9)") (class "Default")
      (node (ref "U6") (pin "9") (pinfunction "0g-Detect_9") (pintype "passive"))
    )
    (net (code "82") (name "unconnected-(U6-NC-Pad1)") (class "Default")
      (node (ref "U6") (pin "1") (pinfunction "NC_1") (pintype "passive+no_connect"))
    )
    (net (code "83") (name "unconnected-(U6-NC-Pad8)") (class "Default")
      (node (ref "U6") (pin "8") (pinfunction "NC_8") (pintype "passive+no_connect"))
    )
    (net (code "84") (name "unconnected-(U6-NC-Pad11)") (class "Default")
      (node (ref "U6") (pin "11") (pinfunction "NC_11") (pintype "passive+no_connect"))
    )
    (net (code "85") (name "unconnected-(U6-NC-Pad12)") (class "Default")
      (node (ref "U6") (pin "12") (pinfunction "NC_12") (pintype "passive+no_connect"))
    )
    (net (code "86") (name "unconnected-(U6-NC-Pad14)") (class "Default")
      (node (ref "U6") (pin "14") (pinfunction "NC_14") (pintype "passive+no_connect"))
    )
  )
)
